# Sheet1.net
KiCad netlist of a schematic drawn in Altium Designer
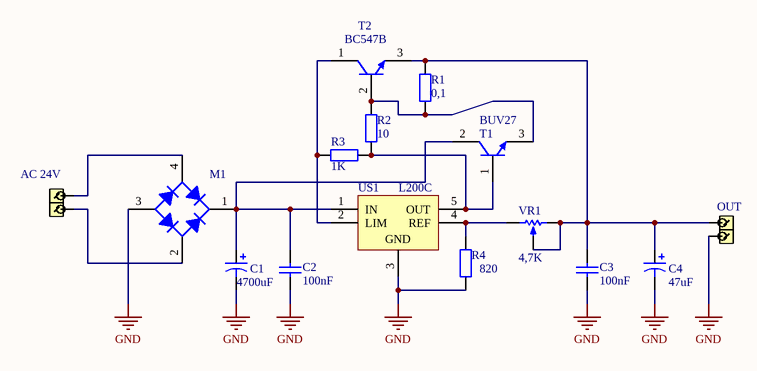
[diagram p0: Sheet1.SchDoc]

(export (version "E")
  (design (tool "Eeschema 10.0.6"))
  (components
    (comp (ref "AC 24V") (value "k") (footprint "ARK2") (libsource (lib "MOJASIM") (part "ARK")))
    (comp (ref "C1")
      (value "4700uF")
      (footprint "CAPPR7.5-16x20")
      (description "Polarized Capacitor (Radial)")
      (fields (field (name "Comment") "Cap Pol1") (field (name "PUBLISHER") "Altium Limited"))
      (libsource (lib "Miscellaneous Devices") (part "Cap Pol1"))
    )
    (comp (ref "C2")
      (value "100nF")
      (footprint "CAPR2.54-5.1x2.5")
      (description "Capacitor (Semiconductor SIM Model)")
      (fields (field (name "Comment") "Cap Semi") (field (name "PUBLISHER") "Altium Limited"))
      (libsource (lib "Miscellaneous Devices") (part "Cap Semi"))
    )
    (comp (ref "C3")
      (value "100nF")
      (footprint "CAPR2.54-5.1x2.5")
      (description "Capacitor (Semiconductor SIM Model)")
      (fields (field (name "Comment") "Cap Semi") (field (name "PUBLISHER") "Altium Limited"))
      (libsource (lib "Miscellaneous Devices") (part "Cap Semi"))
    )
    (comp (ref "C4")
      (value "47uF")
      (footprint "CAPPR5-6.3x15")
      (description "Polarized Capacitor (Radial)")
      (fields (field (name "Comment") "Cap Pol1") (field (name "PUBLISHER") "Altium Limited"))
      (libsource (lib "Miscellaneous Devices") (part "Cap Pol1"))
    )
    (comp (ref "M1")
      (value "Bridge1")
      (footprint "D-38")
      (description "Full Wave Diode Bridge")
      (fields (field (name "PUBLISHER") "Altium Limited"))
      (libsource (lib "Miscellaneous Devices") (part "Bridge1"))
    )
    (comp (ref "OUT") (value "ARK") (footprint "ARK2") (libsource (lib "") (part "ARK_1")))
    (comp (ref "R1")
      (value "0,1")
      (footprint "RES17.7-14X6.5")
      (description "Resistor")
      (fields (field (name "Comment") "Res2") (field (name "PUBLISHER") "Altium Limited"))
      (libsource (lib "") (part "Res2_1"))
    )
    (comp (ref "R2")
      (value "10")
      (footprint "AXIAL-0.4")
      (description "Resistor")
      (fields (field (name "Comment") "Res2") (field (name "PUBLISHER") "Altium Limited"))
      (libsource (lib "Miscellaneous Devices") (part "Res2"))
    )
    (comp (ref "R3")
      (value "1K")
      (footprint "AXIAL-0.4")
      (description "Resistor")
      (fields (field (name "Comment") "Res2") (field (name "PUBLISHER") "Altium Limited"))
      (libsource (lib "") (part "Res2_2"))
    )
    (comp (ref "R4")
      (value "820")
      (footprint "AXIAL-0.4")
      (description "Resistor")
      (fields (field (name "Comment") "Res2") (field (name "PUBLISHER") "Altium Limited"))
      (libsource (lib "Miscellaneous Devices") (part "Res2"))
    )
    (comp (ref "T1")
      (value "BUV27")
      (footprint "ONSC-TO-220-3-221A-09")
      (description "NPN Silicon Power Transistor, 3-Pin TO-220, Tube")
      (fields (field (name "MANUFACTURER") "On Semiconductor"))
      (libsource (lib "ON Semi General Purpose Transistors") (part "BUV27"))
    )
    (comp (ref "T2")
      (value "BC547B")
      (footprint "ONSC-TO-92-3-29-11")
      (description "Amplifier Transistor, NPN Silicon, 3-Pin TO-92, Bulk Box")
      (fields (field (name "MANUFACTURER") "On Semiconductor"))
      (libsource (lib "ON Semi General Purpose Transistors") (part "BC547B"))
    )
    (comp (ref "US1")
      (value "L200C")
      (footprint "PentawattV")
      (description "Adjustable Voltage and Current Regulator, 5-Pin Pentawatt, Tube")
      (fields (field (name "PARTNUMBER") "L200CV"))
      (libsource (lib "ST Microelectronics Power Management Linear Regulator") (part "L200CV"))
    )
    (comp (ref "VR1")
      (value "4,7K")
      (footprint "VR5")
      (description "Potentiometer")
      (fields (field (name "Comment") "RPot") (field (name "PUBLISHER") "Altium Limited"))
      (libsource (lib "Miscellaneous Devices") (part "RPot"))
    )
  )
  (nets
    (net (code "1") (name "GND") (class "Default")
      (node (ref "C1") (pin "2") (pinfunction "2_2") (pintype "passive"))
      (node (ref "C2") (pin "1") (pinfunction "1_1") (pintype "passive"))
      (node (ref "C3") (pin "1") (pinfunction "1_1") (pintype "passive"))
      (node (ref "C4") (pin "2") (pinfunction "2_2") (pintype "passive"))
      (node (ref "M1") (pin "3") (pinfunction "A_3") (pintype "passive"))
      (node (ref "OUT") (pin "1") (pinfunction "1_1") (pintype "passive"))
      (node (ref "R4") (pin "1") (pinfunction "1_1") (pintype "passive"))
      (node (ref "US1") (pin "3") (pinfunction "GND_3") (pintype "power_in"))
    )
    (net (code "2") (name "Net-(AC 24V-Pad1)") (class "Default")
      (node (ref "AC 24V") (pin "1") (pinfunction "1_1") (pintype "passive"))
      (node (ref "M1") (pin "4") (pinfunction "C_4") (pintype "passive"))
    )
    (net (code "3") (name "Net-(AC 24V-Pad2)") (class "Default")
      (node (ref "AC 24V") (pin "2") (pinfunction "2_2") (pintype "passive"))
      (node (ref "M1") (pin "2") (pinfunction "C_2") (pintype "passive"))
    )
    (net (code "4") (name "Net-(M1-K)") (class "Default")
      (node (ref "C1") (pin "1") (pinfunction "1_1") (pintype "passive"))
      (node (ref "C2") (pin "2") (pinfunction "2_2") (pintype "passive"))
      (node (ref "M1") (pin "1") (pinfunction "K_1") (pintype "passive"))
      (node (ref "T1") (pin "2") (pinfunction "C_2") (pintype "passive"))
      (node (ref "US1") (pin "1") (pinfunction "IN_1") (pintype "power_in"))
    )
    (net (code "5") (name "Net-(T1-B)") (class "Default")
      (node (ref "R2") (pin "1") (pinfunction "1_1") (pintype "passive"))
      (node (ref "R3") (pin "1") (pinfunction "1_1") (pintype "passive"))
      (node (ref "T1") (pin "1") (pinfunction "B_1") (pintype "passive"))
      (node (ref "US1") (pin "5") (pinfunction "OUT_5") (pintype "power_in"))
    )
    (net (code "6") (name "Net-(T1-E)") (class "Default")
      (node (ref "R1") (pin "2") (pinfunction "2_2") (pintype "passive"))
      (node (ref "R2") (pin "2") (pinfunction "2_2") (pintype "passive"))
      (node (ref "T1") (pin "3") (pinfunction "E_3") (pintype "passive"))
      (node (ref "T2") (pin "2") (pinfunction "B_2") (pintype "passive"))
    )
    (net (code "7") (name "Net-(T2-C)") (class "Default")
      (node (ref "R3") (pin "2") (pinfunction "2_2") (pintype "passive"))
      (node (ref "T2") (pin "1") (pinfunction "C_1") (pintype "passive"))
      (node (ref "US1") (pin "2") (pinfunction "LIM_2") (pintype "passive"))
    )
    (net (code "8") (name "Net-(T2-E)") (class "Default")
      (node (ref "C3") (pin "2") (pinfunction "2_2") (pintype "passive"))
      (node (ref "C4") (pin "1") (pinfunction "1_1") (pintype "passive"))
      (node (ref "OUT") (pin "2") (pinfunction "2_2") (pintype "passive"))
      (node (ref "R1") (pin "1") (pinfunction "1_1") (pintype "passive"))
      (node (ref "T2") (pin "3") (pinfunction "E_3") (pintype "passive"))
      (node (ref "VR1") (pin "2") (pinfunction "BOT_2") (pintype "passive"))
      (node (ref "VR1") (pin "3") (pinfunction "TAP_3") (pintype "passive"))
    )
    (net (code "9") (name "Net-(US1-REF)") (class "Default")
      (node (ref "R4") (pin "2") (pinfunction "2_2") (pintype "passive"))
      (node (ref "US1") (pin "4") (pinfunction "REF_4") (pintype "passive"))
      (node (ref "VR1") (pin "1") (pinfunction "TOP_1") (pintype "passive"))
    )
  )
)
